# Switched_Outputs.net
KiCad netlist of a schematic drawn in Altium Designer
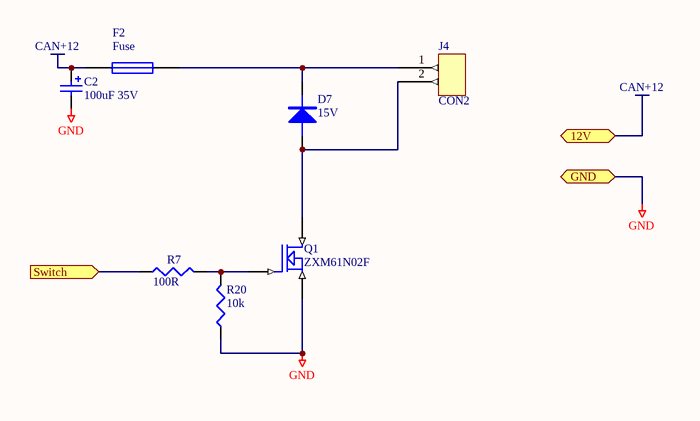
[diagram p0: Switched_Outputs.SchDoc]

(export (version "E")
  (design (tool "Eeschema 10.0.6"))
  (components
    (comp (ref "C2")
      (value "100uF 35V")
      (footprint "MCCT-CASED")
      (description "Polarized Capacitor (Surface Mount)")
      (libsource (lib "Miscellaneous Devices") (part "Cap Pol3"))
    )
    (comp (ref "D7")
      (value "15V")
      (footprint "SMB")
      (description "Diode")
      (libsource (lib "2009_BatteryMaster") (part "DIODE"))
    )
    (comp (ref "F2")
      (value "Fuse")
      (footprint "LITTELFUSE-154")
      (libsource (lib "Miscellaneous") (part "FUSE"))
    )
    (comp (ref "J4")
      (value "CON2")
      (footprint "MICROFIT-2")
      (description "Connector")
      (libsource (lib "*") (part "CON2"))
    )
    (comp (ref "Q1")
      (value "ZXM61N02F")
      (footprint "SOT23(3)")
      (description "1.7A, 20V N-Channel Enhancement mode FET")
      (libsource (lib "RCLDQ") (part "ZXM61N02F"))
    )
    (comp (ref "R7") (value "100R") (footprint "0603") (libsource (lib "*") (part "RES1")))
    (comp (ref "R20") (value "10k") (footprint "0603") (libsource (lib "*") (part "RES1")))
  )
  (nets
    (net (code "1") (name "/Switch") (class "Default")
      (node (ref "R7") (pin "1") (pinfunction "1_1") (pintype "passive"))
    )
    (net (code "2") (name "CAN+12") (class "Default")
      (node (ref "C2") (pin "1") (pinfunction "1_1") (pintype "passive"))
      (node (ref "F2") (pin "1") (pinfunction "1_1") (pintype "passive"))
    )
    (net (code "3") (name "GND") (class "Default")
      (node (ref "C2") (pin "2") (pinfunction "2_2") (pintype "passive"))
      (node (ref "Q1") (pin "2") (pinfunction "S_2") (pintype "input"))
      (node (ref "R20") (pin "1") (pinfunction "1_1") (pintype "passive"))
    )
    (net (code "4") (name "Net-(D7-PadK)") (class "Default")
      (node (ref "D7") (pin "K") (pinfunction "K_K") (pintype "passive"))
      (node (ref "F2") (pin "2") (pinfunction "2_2") (pintype "passive"))
      (node (ref "J4") (pin "1") (pinfunction "1_1") (pintype "output"))
    )
    (net (code "5") (name "Net-(Q1-D)") (class "Default")
      (node (ref "D7") (pin "A") (pinfunction "A_A") (pintype "passive"))
      (node (ref "J4") (pin "2") (pinfunction "2_2") (pintype "output"))
      (node (ref "Q1") (pin "3") (pinfunction "D_3") (pintype "input"))
    )
    (net (code "6") (name "Net-(Q1-G)") (class "Default")
      (node (ref "Q1") (pin "1") (pinfunction "G_1") (pintype "input"))
      (node (ref "R20") (pin "2") (pinfunction "2_2") (pintype "passive"))
      (node (ref "R7") (pin "2") (pinfunction "2_2") (pintype "passive"))
    )
  )
)
